# BalanceBot.net
KiCad netlist of a schematic drawn in EAGLE
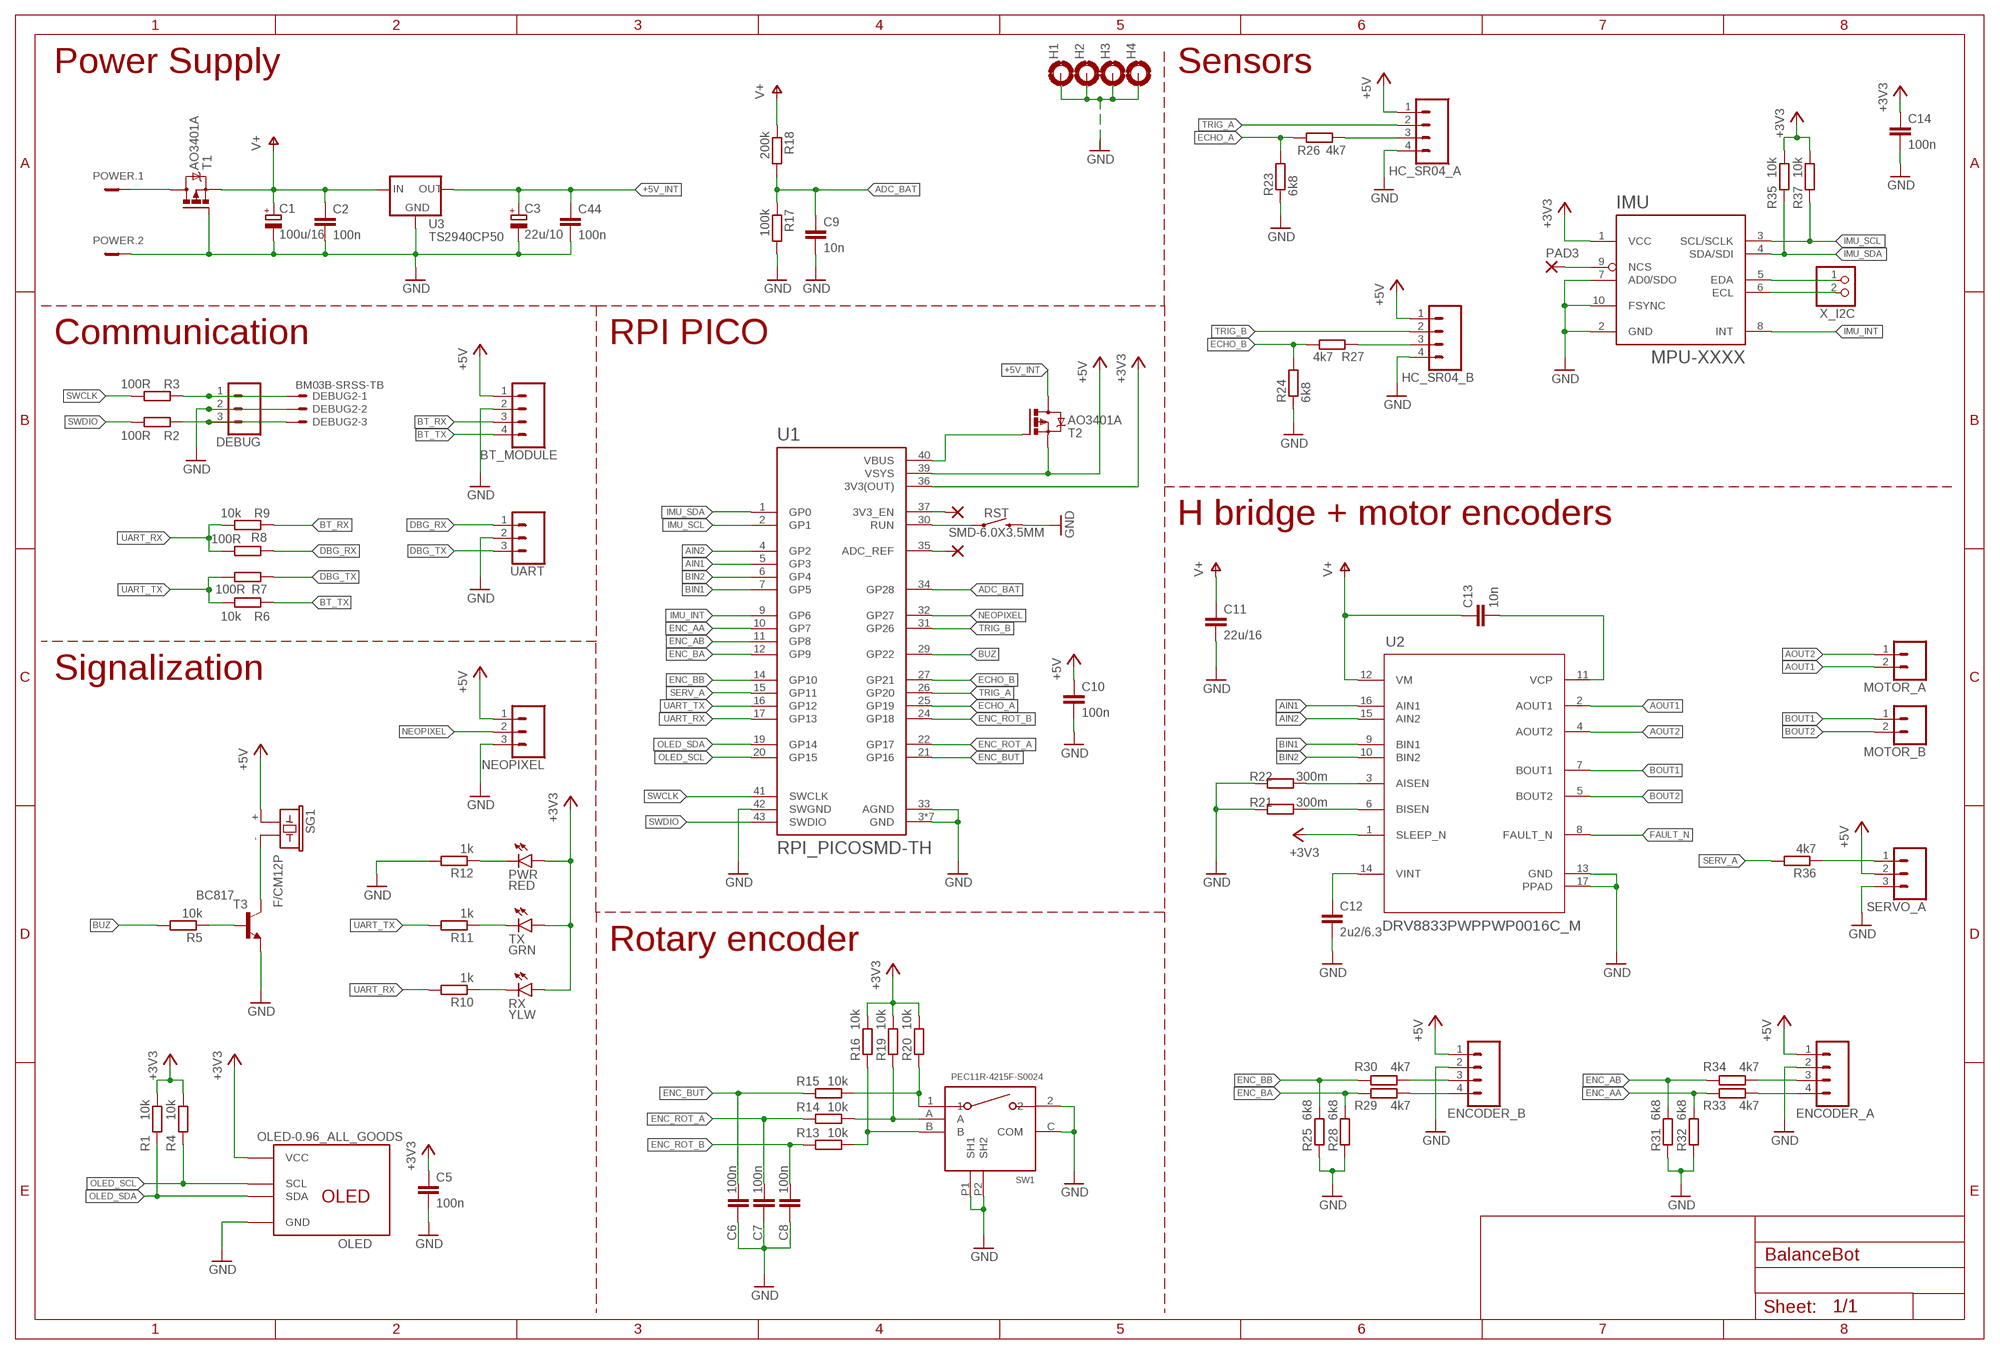
[diagram p0: schematic, sheet 1]

(export (version "E")
  (design (tool "Eeschema 10.0.6"))
  (components
    (comp (ref "BT_MODULE")
      (value "JST-XH-04-PIN-LONG-PAD")
      (footprint "eagle-import:JST-XH-04-PACKAGE-LONG-PAD")
      (libsource (lib "eagle-import") (part "JST-XH-04-PIN-LONG-PAD"))
    )
    (comp (ref "C1")
      (value "100u/16")
      (footprint "eagle-import:E2-5")
      (libsource (lib "eagle-import") (part "CPOL-EUE2-5"))
    )
    (comp (ref "C2")
      (value "100n")
      (footprint "eagle-import:C0805")
      (libsource (lib "eagle-import") (part "C-EUC0805"))
    )
    (comp (ref "C3")
      (value "22u/10")
      (footprint "eagle-import:SMC_B")
      (libsource (lib "eagle-import") (part "CPOL-EUSMCB"))
    )
    (comp (ref "C5")
      (value "100n")
      (footprint "eagle-import:C0805")
      (libsource (lib "eagle-import") (part "C-EUC0805"))
    )
    (comp (ref "C6")
      (value "100n")
      (footprint "eagle-import:C0805")
      (libsource (lib "eagle-import") (part "C-EUC0805"))
    )
    (comp (ref "C7")
      (value "100n")
      (footprint "eagle-import:C0805")
      (libsource (lib "eagle-import") (part "C-EUC0805"))
    )
    (comp (ref "C8")
      (value "100n")
      (footprint "eagle-import:C0805")
      (libsource (lib "eagle-import") (part "C-EUC0805"))
    )
    (comp (ref "C9")
      (value "10n")
      (footprint "eagle-import:C0805")
      (libsource (lib "eagle-import") (part "C-EUC0805"))
    )
    (comp (ref "C10")
      (value "100n")
      (footprint "eagle-import:C0805")
      (libsource (lib "eagle-import") (part "C-EUC0805"))
    )
    (comp (ref "C11")
      (value "22u/16")
      (footprint "eagle-import:C0805")
      (libsource (lib "eagle-import") (part "C-EUC0805"))
    )
    (comp (ref "C12")
      (value "2u2/6.3")
      (footprint "eagle-import:C0805")
      (libsource (lib "eagle-import") (part "C-EUC0805"))
    )
    (comp (ref "C13")
      (value "10n")
      (footprint "eagle-import:C0805")
      (libsource (lib "eagle-import") (part "C-EUC0805"))
    )
    (comp (ref "C14")
      (value "100n")
      (footprint "eagle-import:C0805")
      (libsource (lib "eagle-import") (part "C-EUC0805"))
    )
    (comp (ref "C44")
      (value "100n")
      (footprint "eagle-import:C0805")
      (libsource (lib "eagle-import") (part "C-EUC0805"))
    )
    (comp (ref "DEBUG")
      (value "JST-XH-03-PIN-LONG-PAD")
      (footprint "eagle-import:JST-XH-03-PACKAGE-LONG-PAD")
      (libsource (lib "eagle-import") (part "JST-XH-03-PIN-LONG-PAD"))
    )
    (comp (ref "DEBUG2")
      (value "BM03B-SRSS-TB")
      (footprint "eagle-import:BM03B-SRSS-TB")
      (libsource (lib "eagle-import") (part "?M03B-SRSS-TBB"))
    )
    (comp (ref "ENCODER_A")
      (value "JST-XH-04-PIN-LONG-PAD")
      (footprint "eagle-import:JST-XH-04-PACKAGE-LONG-PAD")
      (libsource (lib "eagle-import") (part "JST-XH-04-PIN-LONG-PAD"))
    )
    (comp (ref "ENCODER_B")
      (value "JST-XH-04-PIN-LONG-PAD")
      (footprint "eagle-import:JST-XH-04-PACKAGE-LONG-PAD")
      (libsource (lib "eagle-import") (part "JST-XH-04-PIN-LONG-PAD"))
    )
    (comp (ref "H1")
      (value "MOUNT-PAD-ROUND3.2")
      (footprint "eagle-import:3,2-PAD")
      (libsource (lib "eagle-import") (part "MOUNT-PAD-ROUND3.2"))
    )
    (comp (ref "H2")
      (value "MOUNT-PAD-ROUND3.2")
      (footprint "eagle-import:3,2-PAD")
      (libsource (lib "eagle-import") (part "MOUNT-PAD-ROUND3.2"))
    )
    (comp (ref "H3")
      (value "MOUNT-PAD-ROUND3.2")
      (footprint "eagle-import:3,2-PAD")
      (libsource (lib "eagle-import") (part "MOUNT-PAD-ROUND3.2"))
    )
    (comp (ref "H4")
      (value "MOUNT-PAD-ROUND3.2")
      (footprint "eagle-import:3,2-PAD")
      (libsource (lib "eagle-import") (part "MOUNT-PAD-ROUND3.2"))
    )
    (comp (ref "HC_SR04_A")
      (value "JST-XH-04-PIN-LONG-PAD")
      (footprint "eagle-import:JST-XH-04-PACKAGE-LONG-PAD")
      (libsource (lib "eagle-import") (part "JST-XH-04-PIN-LONG-PAD"))
    )
    (comp (ref "HC_SR04_B")
      (value "JST-XH-04-PIN-LONG-PAD")
      (footprint "eagle-import:JST-XH-04-PACKAGE-LONG-PAD")
      (libsource (lib "eagle-import") (part "JST-XH-04-PIN-LONG-PAD"))
    )
    (comp (ref "IMU")
      (value "MPU-XXXX")
      (footprint "eagle-import:MPUXXXX")
      (libsource (lib "eagle-import") (part "MPU-XXXX"))
    )
    (comp (ref "MOTOR_A")
      (value "JST-XH-02-PIN-LONG-PAD")
      (footprint "eagle-import:JST-XH-02-PACKAGE-LONG-PAD")
      (libsource (lib "eagle-import") (part "JST-XH-02-PIN-LONG-PAD"))
    )
    (comp (ref "MOTOR_B")
      (value "JST-XH-02-PIN-LONG-PAD")
      (footprint "eagle-import:JST-XH-02-PACKAGE-LONG-PAD")
      (libsource (lib "eagle-import") (part "JST-XH-02-PIN-LONG-PAD"))
    )
    (comp (ref "NEOPIXEL")
      (value "JST-XH-03-PIN-LONG-PAD")
      (footprint "eagle-import:JST-XH-03-PACKAGE-LONG-PAD")
      (libsource (lib "eagle-import") (part "JST-XH-03-PIN-LONG-PAD"))
    )
    (comp (ref "OLED")
      (value "OLED-0.96_ALL_GOODS")
      (footprint "eagle-import:ALL_GOODS")
      (libsource (lib "eagle-import") (part "OLED-0.96_ALL_GOODS"))
    )
    (comp (ref "PAD1")
      (value "WIREPADSMD1,27-254")
      (footprint "eagle-import:SMD1,27-2,54")
      (libsource (lib "eagle-import") (part "WIREPADSMD1,27-254"))
    )
    (comp (ref "PAD2")
      (value "WIREPADSMD1,27-254")
      (footprint "eagle-import:SMD1,27-2,54")
      (libsource (lib "eagle-import") (part "WIREPADSMD1,27-254"))
    )
    (comp (ref "PAD3")
      (value "WIREPADSMD1,27-254")
      (footprint "eagle-import:SMD1,27-2,54")
      (libsource (lib "eagle-import") (part "WIREPADSMD1,27-254"))
    )
    (comp (ref "POWER")
      (value "MCV2")
      (footprint "eagle-import:MCV2")
      (libsource (lib "eagle-import") (part "MCV2"))
    )
    (comp (ref "PWR")
      (value "RED")
      (footprint "eagle-import:CHIP-LED0805")
      (libsource (lib "eagle-import") (part "LEDCHIP-LED0805"))
    )
    (comp (ref "R1")
      (value "10k")
      (footprint "eagle-import:R0805")
      (libsource (lib "eagle-import") (part "R-EU_R0805"))
    )
    (comp (ref "R2")
      (value "100R")
      (footprint "eagle-import:R0805")
      (libsource (lib "eagle-import") (part "R-EU_R0805"))
    )
    (comp (ref "R3")
      (value "100R")
      (footprint "eagle-import:R0805")
      (libsource (lib "eagle-import") (part "R-EU_R0805"))
    )
    (comp (ref "R4")
      (value "10k")
      (footprint "eagle-import:R0805")
      (libsource (lib "eagle-import") (part "R-EU_R0805"))
    )
    (comp (ref "R5")
      (value "10k")
      (footprint "eagle-import:R0805")
      (libsource (lib "eagle-import") (part "R-EU_R0805"))
    )
    (comp (ref "R6")
      (value "10k")
      (footprint "eagle-import:R0805")
      (libsource (lib "eagle-import") (part "R-EU_R0805"))
    )
    (comp (ref "R7")
      (value "100R")
      (footprint "eagle-import:R0805")
      (libsource (lib "eagle-import") (part "R-EU_R0805"))
    )
    (comp (ref "R8")
      (value "100R")
      (footprint "eagle-import:R0805")
      (libsource (lib "eagle-import") (part "R-EU_R0805"))
    )
    (comp (ref "R9")
      (value "10k")
      (footprint "eagle-import:R0805")
      (libsource (lib "eagle-import") (part "R-EU_R0805"))
    )
    (comp (ref "R10")
      (value "1k")
      (footprint "eagle-import:R0805")
      (libsource (lib "eagle-import") (part "R-EU_R0805"))
    )
    (comp (ref "R11")
      (value "1k")
      (footprint "eagle-import:R0805")
      (libsource (lib "eagle-import") (part "R-EU_R0805"))
    )
    (comp (ref "R12")
      (value "1k")
      (footprint "eagle-import:R0805")
      (libsource (lib "eagle-import") (part "R-EU_R0805"))
    )
    (comp (ref "R13")
      (value "10k")
      (footprint "eagle-import:R0805")
      (libsource (lib "eagle-import") (part "R-EU_R0805"))
    )
    (comp (ref "R14")
      (value "10k")
      (footprint "eagle-import:R0805")
      (libsource (lib "eagle-import") (part "R-EU_R0805"))
    )
    (comp (ref "R15")
      (value "10k")
      (footprint "eagle-import:R0805")
      (libsource (lib "eagle-import") (part "R-EU_R0805"))
    )
    (comp (ref "R16")
      (value "10k")
      (footprint "eagle-import:R0805")
      (libsource (lib "eagle-import") (part "R-EU_R0805"))
    )
    (comp (ref "R17")
      (value "100k")
      (footprint "eagle-import:R0805")
      (libsource (lib "eagle-import") (part "R-EU_R0805"))
    )
    (comp (ref "R18")
      (value "200k")
      (footprint "eagle-import:R0805")
      (libsource (lib "eagle-import") (part "R-EU_R0805"))
    )
    (comp (ref "R19")
      (value "10k")
      (footprint "eagle-import:R0805")
      (libsource (lib "eagle-import") (part "R-EU_R0805"))
    )
    (comp (ref "R20")
      (value "10k")
      (footprint "eagle-import:R0805")
      (libsource (lib "eagle-import") (part "R-EU_R0805"))
    )
    (comp (ref "R21")
      (value "300m")
      (footprint "eagle-import:R1206")
      (libsource (lib "eagle-import") (part "R-EU_R1206"))
    )
    (comp (ref "R22")
      (value "300m")
      (footprint "eagle-import:R1206")
      (libsource (lib "eagle-import") (part "R-EU_R1206"))
    )
    (comp (ref "R23")
      (value "6k8")
      (footprint "eagle-import:R0805")
      (libsource (lib "eagle-import") (part "R-EU_R0805"))
    )
    (comp (ref "R24")
      (value "6k8")
      (footprint "eagle-import:R0805")
      (libsource (lib "eagle-import") (part "R-EU_R0805"))
    )
    (comp (ref "R25")
      (value "6k8")
      (footprint "eagle-import:R0805")
      (libsource (lib "eagle-import") (part "R-EU_R0805"))
    )
    (comp (ref "R26")
      (value "4k7")
      (footprint "eagle-import:R0805")
      (libsource (lib "eagle-import") (part "R-EU_R0805"))
    )
    (comp (ref "R27")
      (value "4k7")
      (footprint "eagle-import:R0805")
      (libsource (lib "eagle-import") (part "R-EU_R0805"))
    )
    (comp (ref "R28")
      (value "6k8")
      (footprint "eagle-import:R0805")
      (libsource (lib "eagle-import") (part "R-EU_R0805"))
    )
    (comp (ref "R29")
      (value "4k7")
      (footprint "eagle-import:R0805")
      (libsource (lib "eagle-import") (part "R-EU_R0805"))
    )
    (comp (ref "R30")
      (value "4k7")
      (footprint "eagle-import:R0805")
      (libsource (lib "eagle-import") (part "R-EU_R0805"))
    )
    (comp (ref "R31")
      (value "6k8")
      (footprint "eagle-import:R0805")
      (libsource (lib "eagle-import") (part "R-EU_R0805"))
    )
    (comp (ref "R32")
      (value "6k8")
      (footprint "eagle-import:R0805")
      (libsource (lib "eagle-import") (part "R-EU_R0805"))
    )
    (comp (ref "R33")
      (value "4k7")
      (footprint "eagle-import:R0805")
      (libsource (lib "eagle-import") (part "R-EU_R0805"))
    )
    (comp (ref "R34")
      (value "4k7")
      (footprint "eagle-import:R0805")
      (libsource (lib "eagle-import") (part "R-EU_R0805"))
    )
    (comp (ref "R35")
      (value "10k")
      (footprint "eagle-import:R0805")
      (libsource (lib "eagle-import") (part "R-EU_R0805"))
    )
    (comp (ref "R36")
      (value "4k7")
      (footprint "eagle-import:R0805")
      (libsource (lib "eagle-import") (part "R-EU_R0805"))
    )
    (comp (ref "R37")
      (value "10k")
      (footprint "eagle-import:R0805")
      (libsource (lib "eagle-import") (part "R-EU_R0805"))
    )
    (comp (ref "RST")
      (value "SMD-6.0X3.5MM")
      (footprint "eagle-import:TACTILE_SWITCH_SMD_6.0X3.5MM")
      (libsource (lib "eagle-import") (part "MOMENTARY-SWITCH-SPST-SMD-6.0X3.5MM"))
    )
    (comp (ref "RX")
      (value "YLW")
      (footprint "eagle-import:CHIP-LED0805")
      (libsource (lib "eagle-import") (part "LEDCHIP-LED0805"))
    )
    (comp (ref "SERVO_A")
      (value "JST-XH-03-PIN-LONG-PAD")
      (footprint "eagle-import:JST-XH-03-PACKAGE-LONG-PAD")
      (libsource (lib "eagle-import") (part "JST-XH-03-PIN-LONG-PAD"))
    )
    (comp (ref "SG1")
      (value "F/CM12P")
      (footprint "eagle-import:F_CM12P")
      (libsource (lib "eagle-import") (part "F/CM12P"))
    )
    (comp (ref "SW1")
      (value "PEC11R-4215F-S0024")
      (footprint "eagle-import:PEC11R-4215F-S0024")
      (fields
        (field (name "DIGIKEY_PART_NUMBER") "PEC11R-4215F-S0024-ND")
        (field (name "MANUFACTURER") "Bourns Inc.")
        (field (name "CREATED_BY") "PCBLayout.com")
      )
      (libsource (lib "eagle-import") (part "PEC11R-4215F-S0024"))
    )
    (comp (ref "T1")
      (value "AO3401A")
      (footprint "eagle-import:SOT23")
      (libsource (lib "eagle-import") (part "PMOSFETSOT23-GSD_"))
    )
    (comp (ref "T2")
      (value "AO3401A")
      (footprint "eagle-import:SOT23")
      (libsource (lib "eagle-import") (part "PMOSFETSOT23-GSD_"))
    )
    (comp (ref "T3")
      (value "BC817")
      (footprint "eagle-import:SOT23-BEC")
      (libsource (lib "eagle-import") (part "-NPN-SOT23-BECBC817"))
    )
    (comp (ref "TX")
      (value "GRN")
      (footprint "eagle-import:CHIP-LED0805")
      (libsource (lib "eagle-import") (part "LEDCHIP-LED0805"))
    )
    (comp (ref "U1")
      (value "RPI_PICOSMD-TH")
      (footprint "eagle-import:PICO-PKG-TH-ONLY")
      (libsource (lib "eagle-import") (part "RASPBERRY_PICOTH-ONLY"))
    )
    (comp (ref "U2")
      (value "DRV8833PWPPWP0016C_M")
      (footprint "eagle-import:PWP0016C_M")
      (fields
        (field (name "MANUFACTURER_PART_NUMBER") "DRV8833PWP")
        (field (name "COPYRIGHT") "Copyright (C) 2023 Ultra Librarian. All rights reserved.")
      )
      (libsource (lib "eagle-import") (part "DRV8833PWPPWP0016C_M"))
    )
    (comp (ref "U3")
      (value "TS2940CP50")
      (footprint "eagle-import:DPACK")
      (libsource (lib "eagle-import") (part "LP2950?CDT-5.0"))
    )
    (comp (ref "UART")
      (value "JST-XH-03-PIN-LONG-PAD")
      (footprint "eagle-import:JST-XH-03-PACKAGE-LONG-PAD")
      (libsource (lib "eagle-import") (part "JST-XH-03-PIN-LONG-PAD"))
    )
    (comp (ref "X_I2C")
      (value "PINHD-1X2")
      (footprint "eagle-import:1X02")
      (libsource (lib "eagle-import") (part "PINHD-1X2"))
    )
  )
  (nets
    (net (code "1") (name "+3V3") (class "Default")
      (node (ref "C14") (pin "1") (pinfunction "1_1") (pintype "passive"))
      (node (ref "C5") (pin "1") (pinfunction "1_1") (pintype "passive"))
      (node (ref "IMU") (pin "1") (pinfunction "VCC_1") (pintype "power_in"))
      (node (ref "OLED") (pin "2") (pinfunction "VCC_2") (pintype "power_in"))
      (node (ref "PWR") (pin "A") (pinfunction "A_A") (pintype "passive"))
      (node (ref "R1") (pin "1") (pinfunction "1_1") (pintype "passive"))
      (node (ref "R16") (pin "1") (pinfunction "1_1") (pintype "passive"))
      (node (ref "R19") (pin "1") (pinfunction "1_1") (pintype "passive"))
      (node (ref "R20") (pin "1") (pinfunction "1_1") (pintype "passive"))
      (node (ref "R35") (pin "1") (pinfunction "1_1") (pintype "passive"))
      (node (ref "R37") (pin "1") (pinfunction "1_1") (pintype "passive"))
      (node (ref "R4") (pin "1") (pinfunction "1_1") (pintype "passive"))
      (node (ref "RX") (pin "A") (pinfunction "A_A") (pintype "passive"))
      (node (ref "TX") (pin "A") (pinfunction "A_A") (pintype "passive"))
      (node (ref "U1") (pin "36") (pinfunction "3V3(OUT)_36") (pintype "power_in"))
      (node (ref "U2") (pin "1") (pinfunction "SLEEP_N_1") (pintype "input"))
    )
    (net (code "2") (name "+5V") (class "Default")
      (node (ref "BT_MODULE") (pin "1") (pinfunction "1_1") (pintype "passive"))
      (node (ref "C10") (pin "1") (pinfunction "1_1") (pintype "passive"))
      (node (ref "ENCODER_A") (pin "1") (pinfunction "1_1") (pintype "passive"))
      (node (ref "ENCODER_B") (pin "1") (pinfunction "1_1") (pintype "passive"))
      (node (ref "HC_SR04_A") (pin "1") (pinfunction "1_1") (pintype "passive"))
      (node (ref "HC_SR04_B") (pin "1") (pinfunction "1_1") (pintype "passive"))
      (node (ref "NEOPIXEL") (pin "1") (pinfunction "1_1") (pintype "passive"))
      (node (ref "SERVO_A") (pin "2") (pinfunction "2_2") (pintype "passive"))
      (node (ref "SG1") (pin "+") (pinfunction "1_+") (pintype "passive"))
      (node (ref "T2") (pin "2") (pinfunction "S_2") (pintype "passive"))
      (node (ref "U1") (pin "39") (pinfunction "VSYS_39") (pintype "power_in"))
    )
    (net (code "3") (name "+5V_INT") (class "Default")
      (node (ref "C3") (pin "+") (pinfunction "+_+") (pintype "passive"))
      (node (ref "C44") (pin "1") (pinfunction "1_1") (pintype "passive"))
      (node (ref "T2") (pin "3") (pinfunction "D_3") (pintype "passive"))
      (node (ref "U3") (pin "3") (pinfunction "OUT_3") (pintype "passive"))
    )
    (net (code "4") (name "ADC_BAT") (class "Default")
      (node (ref "C9") (pin "1") (pinfunction "1_1") (pintype "passive"))
      (node (ref "R17") (pin "1") (pinfunction "1_1") (pintype "passive"))
      (node (ref "R18") (pin "2") (pinfunction "2_2") (pintype "passive"))
      (node (ref "U1") (pin "34") (pinfunction "GP28_34") (pintype "bidirectional"))
    )
    (net (code "5") (name "AIN1") (class "Default")
      (node (ref "U1") (pin "5") (pinfunction "GP3_5") (pintype "bidirectional"))
      (node (ref "U2") (pin "16") (pinfunction "AIN1_16") (pintype "input"))
    )
    (net (code "6") (name "AIN2") (class "Default")
      (node (ref "U1") (pin "4") (pinfunction "GP2_4") (pintype "bidirectional"))
      (node (ref "U2") (pin "15") (pinfunction "AIN2_15") (pintype "input"))
    )
    (net (code "7") (name "AOUT1") (class "Default")
      (node (ref "MOTOR_A") (pin "2") (pinfunction "2_2") (pintype "passive"))
      (node (ref "U2") (pin "2") (pinfunction "AOUT1_2") (pintype "tri_state"))
    )
    (net (code "8") (name "AOUT2") (class "Default")
      (node (ref "MOTOR_A") (pin "1") (pinfunction "1_1") (pintype "passive"))
      (node (ref "U2") (pin "4") (pinfunction "AOUT2_4") (pintype "tri_state"))
    )
    (net (code "9") (name "BIN1") (class "Default")
      (node (ref "U1") (pin "7") (pinfunction "GP5_7") (pintype "bidirectional"))
      (node (ref "U2") (pin "9") (pinfunction "BIN1_9") (pintype "input"))
    )
    (net (code "10") (name "BIN2") (class "Default")
      (node (ref "U1") (pin "6") (pinfunction "GP4_6") (pintype "bidirectional"))
      (node (ref "U2") (pin "10") (pinfunction "BIN2_10") (pintype "input"))
    )
    (net (code "11") (name "BOUT1") (class "Default")
      (node (ref "MOTOR_B") (pin "1") (pinfunction "1_1") (pintype "passive"))
      (node (ref "U2") (pin "7") (pinfunction "BOUT1_7") (pintype "tri_state"))
    )
    (net (code "12") (name "BOUT2") (class "Default")
      (node (ref "MOTOR_B") (pin "2") (pinfunction "2_2") (pintype "passive"))
      (node (ref "U2") (pin "5") (pinfunction "BOUT2_5") (pintype "tri_state"))
    )
    (net (code "13") (name "BT_RX") (class "Default")
      (node (ref "BT_MODULE") (pin "3") (pinfunction "3_3") (pintype "passive"))
      (node (ref "R9") (pin "1") (pinfunction "1_1") (pintype "passive"))
    )
    (net (code "14") (name "BT_TX") (class "Default")
      (node (ref "BT_MODULE") (pin "4") (pinfunction "4_4") (pintype "passive"))
      (node (ref "R6") (pin "1") (pinfunction "1_1") (pintype "passive"))
    )
    (net (code "15") (name "BUZ") (class "Default")
      (node (ref "R5") (pin "2") (pinfunction "2_2") (pintype "passive"))
      (node (ref "U1") (pin "29") (pinfunction "GP22_29") (pintype "bidirectional"))
    )
    (net (code "16") (name "DBG_RX") (class "Default")
      (node (ref "R8") (pin "1") (pinfunction "1_1") (pintype "passive"))
      (node (ref "UART") (pin "1") (pinfunction "1_1") (pintype "passive"))
    )
    (net (code "17") (name "DBG_TX") (class "Default")
      (node (ref "R7") (pin "1") (pinfunction "1_1") (pintype "passive"))
      (node (ref "UART") (pin "3") (pinfunction "3_3") (pintype "passive"))
    )
    (net (code "18") (name "ECHO_A") (class "Default")
      (node (ref "R23") (pin "2") (pinfunction "2_2") (pintype "passive"))
      (node (ref "R26") (pin "1") (pinfunction "1_1") (pintype "passive"))
      (node (ref "U1") (pin "25") (pinfunction "GP19_25") (pintype "bidirectional"))
    )
    (net (code "19") (name "ECHO_B") (class "Default")
      (node (ref "R24") (pin "2") (pinfunction "2_2") (pintype "passive"))
      (node (ref "R27") (pin "1") (pinfunction "1_1") (pintype "passive"))
      (node (ref "U1") (pin "27") (pinfunction "GP21_27") (pintype "bidirectional"))
    )
    (net (code "20") (name "ENC_AA") (class "Default")
      (node (ref "R32") (pin "2") (pinfunction "2_2") (pintype "passive"))
      (node (ref "R33") (pin "1") (pinfunction "1_1") (pintype "passive"))
      (node (ref "U1") (pin "10") (pinfunction "GP7_10") (pintype "bidirectional"))
    )
    (net (code "21") (name "ENC_AB") (class "Default")
      (node (ref "R31") (pin "2") (pinfunction "2_2") (pintype "passive"))
      (node (ref "R34") (pin "2") (pinfunction "2_2") (pintype "passive"))
      (node (ref "U1") (pin "11") (pinfunction "GP8_11") (pintype "bidirectional"))
    )
    (net (code "22") (name "ENC_BA") (class "Default")
      (node (ref "R28") (pin "2") (pinfunction "2_2") (pintype "passive"))
      (node (ref "R29") (pin "1") (pinfunction "1_1") (pintype "passive"))
      (node (ref "U1") (pin "12") (pinfunction "GP9_12") (pintype "bidirectional"))
    )
    (net (code "23") (name "ENC_BB") (class "Default")
      (node (ref "R25") (pin "2") (pinfunction "2_2") (pintype "passive"))
      (node (ref "R30") (pin "2") (pinfunction "2_2") (pintype "passive"))
      (node (ref "U1") (pin "14") (pinfunction "GP10_14") (pintype "bidirectional"))
    )
    (net (code "24") (name "ENC_BUT") (class "Default")
      (node (ref "C6") (pin "1") (pinfunction "1_1") (pintype "passive"))
      (node (ref "R15") (pin "1") (pinfunction "1_1") (pintype "passive"))
      (node (ref "U1") (pin "21") (pinfunction "GP16_21") (pintype "bidirectional"))
    )
    (net (code "25") (name "ENC_ROT_A") (class "Default")
      (node (ref "C7") (pin "1") (pinfunction "1_1") (pintype "passive"))
      (node (ref "R14") (pin "1") (pinfunction "1_1") (pintype "passive"))
      (node (ref "U1") (pin "22") (pinfunction "GP17_22") (pintype "bidirectional"))
    )
    (net (code "26") (name "ENC_ROT_B") (class "Default")
      (node (ref "C8") (pin "1") (pinfunction "1_1") (pintype "passive"))
      (node (ref "R13") (pin "1") (pinfunction "1_1") (pintype "passive"))
      (node (ref "U1") (pin "24") (pinfunction "GP18_24") (pintype "bidirectional"))
    )
    (net (code "27") (name "FAULT_N") (class "Default")
      (node (ref "U2") (pin "8") (pinfunction "FAULT_N_8") (pintype "open_collector"))
    )
    (net (code "28") (name "GND") (class "Default")
      (node (ref "BT_MODULE") (pin "2") (pinfunction "2_2") (pintype "passive"))
      (node (ref "C1") (pin "-") (pinfunction "-_-") (pintype "passive"))
      (node (ref "C10") (pin "2") (pinfunction "2_2") (pintype "passive"))
      (node (ref "C11") (pin "2") (pinfunction "2_2") (pintype "passive"))
      (node (ref "C12") (pin "2") (pinfunction "2_2") (pintype "passive"))
      (node (ref "C14") (pin "2") (pinfunction "2_2") (pintype "passive"))
      (node (ref "C2") (pin "2") (pinfunction "2_2") (pintype "passive"))
      (node (ref "C3") (pin "-") (pinfunction "-_-") (pintype "passive"))
      (node (ref "C44") (pin "2") (pinfunction "2_2") (pintype "passive"))
      (node (ref "C5") (pin "2") (pinfunction "2_2") (pintype "passive"))
      (node (ref "C6") (pin "2") (pinfunction "2_2") (pintype "passive"))
      (node (ref "C7") (pin "2") (pinfunction "2_2") (pintype "passive"))
      (node (ref "C8") (pin "2") (pinfunction "2_2") (pintype "passive"))
      (node (ref "C9") (pin "2") (pinfunction "2_2") (pintype "passive"))
      (node (ref "DEBUG") (pin "2") (pinfunction "2_2") (pintype "passive"))
      (node (ref "DEBUG2") (pin "2") (pinfunction "S_2") (pintype "passive"))
      (node (ref "ENCODER_A") (pin "2") (pinfunction "2_2") (pintype "passive"))
      (node (ref "ENCODER_B") (pin "2") (pinfunction "2_2") (pintype "passive"))
      (node (ref "H1") (pin "B3,2") (pinfunction "MOUNT_B3,2") (pintype "passive"))
      (node (ref "H2") (pin "B3,2") (pinfunction "MOUNT_B3,2") (pintype "passive"))
      (node (ref "H3") (pin "B3,2") (pinfunction "MOUNT_B3,2") (pintype "passive"))
      (node (ref "H4") (pin "B3,2") (pinfunction "MOUNT_B3,2") (pintype "passive"))
      (node (ref "HC_SR04_A") (pin "4") (pinfunction "4_4") (pintype "passive"))
      (node (ref "HC_SR04_B") (pin "4") (pinfunction "4_4") (pintype "passive"))
      (node (ref "IMU") (pin "10") (pinfunction "FSYNC_10") (pintype "input"))
      (node (ref "IMU") (pin "2") (pinfunction "GND_2") (pintype "power_in"))
      (node (ref "IMU") (pin "7") (pinfunction "AD0/SDO_7") (pintype "input"))
      (node (ref "NEOPIXEL") (pin "3") (pinfunction "3_3") (pintype "passive"))
      (node (ref "OLED") (pin "1") (pinfunction "GND_1") (pintype "power_in"))
      (node (ref "POWER") (pin "2") (pinfunction "SK_2") (pintype "passive"))
      (node (ref "R12") (pin "2") (pinfunction "2_2") (pintype "passive"))
      (node (ref "R17") (pin "2") (pinfunction "2_2") (pintype "passive"))
      (node (ref "R21") (pin "1") (pinfunction "1_1") (pintype "passive"))
      (node (ref "R22") (pin "1") (pinfunction "1_1") (pintype "passive"))
      (node (ref "R23") (pin "1") (pinfunction "1_1") (pintype "passive"))
      (node (ref "R24") (pin "1") (pinfunction "1_1") (pintype "passive"))
      (node (ref "R25") (pin "1") (pinfunction "1_1") (pintype "passive"))
      (node (ref "R28") (pin "1") (pinfunction "1_1") (pintype "passive"))
      (node (ref "R31") (pin "1") (pinfunction "1_1") (pintype "passive"))
      (node (ref "R32") (pin "1") (pinfunction "1_1") (pintype "passive"))
      (node (ref "RST") (pin "2") (pinfunction "2_2") (pintype "passive"))
      (node (ref "SERVO_A") (pin "3") (pinfunction "3_3") (pintype "passive"))
      (node (ref "SW1") (pin "2") (pinfunction "2_2") (pintype "passive"))
      (node (ref "SW1") (pin "C") (pinfunction "COM_C") (pintype "passive"))
      (node (ref "SW1") (pin "P1") (pinfunction "SH1_P1") (pintype "power_in"))
      (node (ref "SW1") (pin "P2") (pinfunction "SH2_P2") (pintype "power_in"))
      (node (ref "T1") (pin "1") (pinfunction "G_1") (pintype "passive"))
      (node (ref "T3") (pin "E") (pinfunction "E_E") (pintype "passive"))
      (node (ref "U1") (pin "13") (pinfunction "GND_13") (pintype "power_in"))
      (node (ref "U1") (pin "18") (pinfunction "GND_18") (pintype "power_in"))
      (node (ref "U1") (pin "23") (pinfunction "GND_23") (pintype "power_in"))
      (node (ref "U1") (pin "28") (pinfunction "GND_28") (pintype "power_in"))
      (node (ref "U1") (pin "3") (pinfunction "GND_3") (pintype "power_in"))
      (node (ref "U1") (pin "33") (pinfunction "AGND_33") (pintype "power_in"))
      (node (ref "U1") (pin "38") (pinfunction "GND_38") (pintype "power_in"))
      (node (ref "U1") (pin "42") (pinfunction "SWGND_42") (pintype "power_in"))
      (node (ref "U1") (pin "8") (pinfunction "GND_8") (pintype "power_in"))
      (node (ref "U2") (pin "13") (pinfunction "GND_13") (pintype "power_in"))
      (node (ref "U2") (pin "17") (pinfunction "PPAD_17") (pintype "power_in"))
      (node (ref "U3") (pin "4") (pinfunction "GND_4") (pintype "input"))
      (node (ref "UART") (pin "2") (pinfunction "2_2") (pintype "passive"))
    )
    (net (code "29") (name "IMU_INT") (class "Default")
      (node (ref "IMU") (pin "8") (pinfunction "INT_8") (pintype "output"))
      (node (ref "U1") (pin "9") (pinfunction "GP6_9") (pintype "bidirectional"))
    )
    (net (code "30") (name "IMU_SCL") (class "Default")
      (node (ref "IMU") (pin "3") (pinfunction "SCL/SCLK_3") (pintype "bidirectional"))
      (node (ref "R37") (pin "2") (pinfunction "2_2") (pintype "passive"))
      (node (ref "U1") (pin "2") (pinfunction "GP1_2") (pintype "bidirectional"))
    )
    (net (code "31") (name "IMU_SDA") (class "Default")
      (node (ref "IMU") (pin "4") (pinfunction "SDA/SDI_4") (pintype "bidirectional"))
      (node (ref "R35") (pin "2") (pinfunction "2_2") (pintype "passive"))
      (node (ref "U1") (pin "1") (pinfunction "GP0_1") (pintype "bidirectional"))
    )
    (net (code "32") (name "NEOPIXEL") (class "Default")
      (node (ref "NEOPIXEL") (pin "2") (pinfunction "2_2") (pintype "passive"))
      (node (ref "U1") (pin "32") (pinfunction "GP27_32") (pintype "bidirectional"))
    )
    (net (code "33") (name "Net-(DEBUG2A-S)") (class "Default")
      (node (ref "DEBUG") (pin "1") (pinfunction "1_1") (pintype "passive"))
      (node (ref "DEBUG2") (pin "1") (pinfunction "S_1") (pintype "passive"))
      (node (ref "R3") (pin "1") (pinfunction "1_1") (pintype "passive"))
    )
    (net (code "34") (name "Net-(DEBUG2C-S)") (class "Default")
      (node (ref "DEBUG") (pin "3") (pinfunction "3_3") (pintype "passive"))
      (node (ref "DEBUG2") (pin "3") (pinfunction "S_3") (pintype "passive"))
      (node (ref "R2") (pin "2") (pinfunction "2_2") (pintype "passive"))
    )
    (net (code "35") (name "Net-(ENCODER_A-Pad3)") (class "Default")
      (node (ref "ENCODER_A") (pin "3") (pinfunction "3_3") (pintype "passive"))
      (node (ref "R34") (pin "1") (pinfunction "1_1") (pintype "passive"))
    )
    (net (code "36") (name "Net-(ENCODER_A-Pad4)") (class "Default")
      (node (ref "ENCODER_A") (pin "4") (pinfunction "4_4") (pintype "passive"))
      (node (ref "R33") (pin "2") (pinfunction "2_2") (pintype "passive"))
    )
    (net (code "37") (name "Net-(ENCODER_B-Pad3)") (class "Default")
      (node (ref "ENCODER_B") (pin "3") (pinfunction "3_3") (pintype "passive"))
      (node (ref "R30") (pin "1") (pinfunction "1_1") (pintype "passive"))
    )
    (net (code "38") (name "Net-(ENCODER_B-Pad4)") (class "Default")
      (node (ref "ENCODER_B") (pin "4") (pinfunction "4_4") (pintype "passive"))
      (node (ref "R29") (pin "2") (pinfunction "2_2") (pintype "passive"))
    )
    (net (code "39") (name "Net-(HC_SR04_A-Pad3)") (class "Default")
      (node (ref "HC_SR04_A") (pin "3") (pinfunction "3_3") (pintype "passive"))
      (node (ref "R26") (pin "2") (pinfunction "2_2") (pintype "passive"))
    )
    (net (code "40") (name "Net-(HC_SR04_B-Pad3)") (class "Default")
      (node (ref "HC_SR04_B") (pin "3") (pinfunction "3_3") (pintype "passive"))
      (node (ref "R27") (pin "2") (pinfunction "2_2") (pintype "passive"))
    )
    (net (code "41") (name "Net-(IMU-ECL)") (class "Default")
      (node (ref "IMU") (pin "6") (pinfunction "ECL_6") (pintype "bidirectional"))
      (node (ref "X_I2C") (pin "2") (pinfunction "2_2") (pintype "passive"))
    )
    (net (code "42") (name "Net-(IMU-EDA)") (class "Default")
      (node (ref "IMU") (pin "5") (pinfunction "EDA_5") (pintype "bidirectional"))
      (node (ref "X_I2C") (pin "1") (pinfunction "1_1") (pintype "passive"))
    )
    (net (code "43") (name "Net-(IMU-NCS)") (class "Default")
      (node (ref "IMU") (pin "9") (pinfunction "NCS_9") (pintype "input"))
      (node (ref "PAD3") (pin "1") (pinfunction "P_1") (pintype "passive"))
    )
    (net (code "44") (name "Net-(PAD1-P)") (class "Default")
      (node (ref "PAD1") (pin "1") (pinfunction "P_1") (pintype "passive"))
      (node (ref "U1") (pin "35") (pinfunction "ADC_REF_35") (pintype "input"))
    )
    (net (code "45") (name "Net-(PAD2-P)") (class "Default")
      (node (ref "PAD2") (pin "1") (pinfunction "P_1") (pintype "passive"))
      (node (ref "U1") (pin "37") (pinfunction "3V3_EN_37") (pintype "input"))
    )
    (net (code "46") (name "Net-(POWERA-SK)") (class "Default")
      (node (ref "POWER") (pin "1") (pinfunction "SK_1") (pintype "passive"))
      (node (ref "T1") (pin "3") (pinfunction "D_3") (pintype "passive"))
    )
    (net (code "47") (name "Net-(PWR-PadC)") (class "Default")
      (node (ref "PWR") (pin "C") (pinfunction "C_C") (pintype "passive"))
      (node (ref "R12") (pin "1") (pinfunction "1_1") (pintype "passive"))
    )
    (net (code "48") (name "Net-(R5-Pad1)") (class "Default")
      (node (ref "R5") (pin "1") (pinfunction "1_1") (pintype "passive"))
      (node (ref "T3") (pin "B") (pinfunction "B_B") (pintype "passive"))
    )
    (net (code "49") (name "Net-(R10-Pad1)") (class "Default")
      (node (ref "R10") (pin "1") (pinfunction "1_1") (pintype "passive"))
      (node (ref "RX") (pin "C") (pinfunction "C_C") (pintype "passive"))
    )
    (net (code "50") (name "Net-(R11-Pad1)") (class "Default")
      (node (ref "R11") (pin "1") (pinfunction "1_1") (pintype "passive"))
      (node (ref "TX") (pin "C") (pinfunction "C_C") (pintype "passive"))
    )
    (net (code "51") (name "Net-(R13-Pad2)") (class "Default")
      (node (ref "R13") (pin "2") (pinfunction "2_2") (pintype "passive"))
      (node (ref "R16") (pin "2") (pinfunction "2_2") (pintype "passive"))
      (node (ref "SW1") (pin "B") (pinfunction "B_B") (pintype "passive"))
    )
    (net (code "52") (name "Net-(R14-Pad2)") (class "Default")
      (node (ref "R14") (pin "2") (pinfunction "2_2") (pintype "passive"))
      (node (ref "R19") (pin "2") (pinfunction "2_2") (pintype "passive"))
      (node (ref "SW1") (pin "A") (pinfunction "A_A") (pintype "passive"))
    )
    (net (code "53") (name "Net-(R15-Pad2)") (class "Default")
      (node (ref "R15") (pin "2") (pinfunction "2_2") (pintype "passive"))
      (node (ref "R20") (pin "2") (pinfunction "2_2") (pintype "passive"))
      (node (ref "SW1") (pin "1") (pinfunction "1_1") (pintype "passive"))
    )
    (net (code "54") (name "Net-(R36-Pad1)") (class "Default")
      (node (ref "R36") (pin "1") (pinfunction "1_1") (pintype "passive"))
      (node (ref "SERVO_A") (pin "1") (pinfunction "1_1") (pintype "passive"))
    )
    (net (code "55") (name "Net-(SG1-2)") (class "Default")
      (node (ref "SG1") (pin "-") (pinfunction "2_-") (pintype "passive"))
      (node (ref "T3") (pin "C") (pinfunction "C_C") (pintype "passive"))
    )
    (net (code "56") (name "Net-(T2-G)") (class "Default")
      (node (ref "T2") (pin "1") (pinfunction "G_1") (pintype "passive"))
      (node (ref "U1") (pin "40") (pinfunction "VBUS_40") (pintype "power_in"))
    )
    (net (code "57") (name "Net-(U1-RUN)") (class "Default")
      (node (ref "RST") (pin "1") (pinfunction "1_1") (pintype "passive"))
      (node (ref "U1") (pin "30") (pinfunction "RUN_30") (pintype "input"))
    )
    (net (code "58") (name "Net-(U2-AISEN)") (class "Default")
      (node (ref "R22") (pin "2") (pinfunction "2_2") (pintype "passive"))
      (node (ref "U2") (pin "3") (pinfunction "AISEN_3") (pintype "input"))
    )
    (net (code "59") (name "Net-(U2-BISEN)") (class "Default")
      (node (ref "R21") (pin "2") (pinfunction "2_2") (pintype "passive"))
      (node (ref "U2") (pin "6") (pinfunction "BISEN_6") (pintype "input"))
    )
    (net (code "60") (name "Net-(U2-VCP)") (class "Default")
      (node (ref "C13") (pin "2") (pinfunction "2_2") (pintype "passive"))
      (node (ref "U2") (pin "11") (pinfunction "VCP_11") (pintype "bidirectional"))
    )
    (net (code "61") (name "Net-(U2-VINT)") (class "Default")
      (node (ref "C12") (pin "1") (pinfunction "1_1") (pintype "passive"))
      (node (ref "U2") (pin "14") (pinfunction "VINT_14") (pintype "passive"))
    )
    (net (code "62") (name "OLED_SCL") (class "Default")
      (node (ref "OLED") (pin "3") (pinfunction "SCL_3") (pintype "input"))
      (node (ref "R4") (pin "2") (pinfunction "2_2") (pintype "passive"))
      (node (ref "U1") (pin "20") (pinfunction "GP15_20") (pintype "bidirectional"))
    )
    (net (code "63") (name "OLED_SDA") (class "Default")
      (node (ref "OLED") (pin "4") (pinfunction "SDA_4") (pintype "input"))
      (node (ref "R1") (pin "2") (pinfunction "2_2") (pintype "passive"))
      (node (ref "U1") (pin "19") (pinfunction "GP14_19") (pintype "bidirectional"))
    )
    (net (code "64") (name "SERV_A") (class "Default")
      (node (ref "R36") (pin "2") (pinfunction "2_2") (pintype "passive"))
      (node (ref "U1") (pin "15") (pinfunction "GP11_15") (pintype "bidirectional"))
    )
    (net (code "65") (name "SWCLK") (class "Default")
      (node (ref "R3") (pin "2") (pinfunction "2_2") (pintype "passive"))
      (node (ref "U1") (pin "41") (pinfunction "SWCLK_41") (pintype "input"))
    )
    (net (code "66") (name "SWDIO") (class "Default")
      (node (ref "R2") (pin "1") (pinfunction "1_1") (pintype "passive"))
      (node (ref "U1") (pin "43") (pinfunction "SWDIO_43") (pintype "bidirectional"))
    )
    (net (code "67") (name "TRIG_A") (class "Default")
      (node (ref "HC_SR04_A") (pin "2") (pinfunction "2_2") (pintype "passive"))
      (node (ref "U1") (pin "26") (pinfunction "GP20_26") (pintype "bidirectional"))
    )
    (net (code "68") (name "TRIG_B") (class "Default")
      (node (ref "HC_SR04_B") (pin "2") (pinfunction "2_2") (pintype "passive"))
      (node (ref "U1") (pin "31") (pinfunction "GP26_31") (pintype "bidirectional"))
    )
    (net (code "69") (name "UART_RX") (class "Default")
      (node (ref "R10") (pin "2") (pinfunction "2_2") (pintype "passive"))
      (node (ref "R8") (pin "2") (pinfunction "2_2") (pintype "passive"))
      (node (ref "R9") (pin "2") (pinfunction "2_2") (pintype "passive"))
      (node (ref "U1") (pin "17") (pinfunction "GP13_17") (pintype "bidirectional"))
    )
    (net (code "70") (name "UART_TX") (class "Default")
      (node (ref "R11") (pin "2") (pinfunction "2_2") (pintype "passive"))
      (node (ref "R6") (pin "2") (pinfunction "2_2") (pintype "passive"))
      (node (ref "R7") (pin "2") (pinfunction "2_2") (pintype "passive"))
      (node (ref "U1") (pin "16") (pinfunction "GP12_16") (pintype "bidirectional"))
    )
    (net (code "71") (name "V+") (class "Default")
      (node (ref "C1") (pin "+") (pinfunction "+_+") (pintype "passive"))
      (node (ref "C11") (pin "1") (pinfunction "1_1") (pintype "passive"))
      (node (ref "C13") (pin "1") (pinfunction "1_1") (pintype "passive"))
      (node (ref "C2") (pin "1") (pinfunction "1_1") (pintype "passive"))
      (node (ref "R18") (pin "1") (pinfunction "1_1") (pintype "passive"))
      (node (ref "T1") (pin "2") (pinfunction "S_2") (pintype "passive"))
      (node (ref "U2") (pin "12") (pinfunction "VM_12") (pintype "power_in"))
      (node (ref "U3") (pin "1") (pinfunction "IN_1") (pintype "input"))
    )
  )
)
